# led_board_v2-3hole.net
KiCad netlist of a schematic drawn in EAGLE
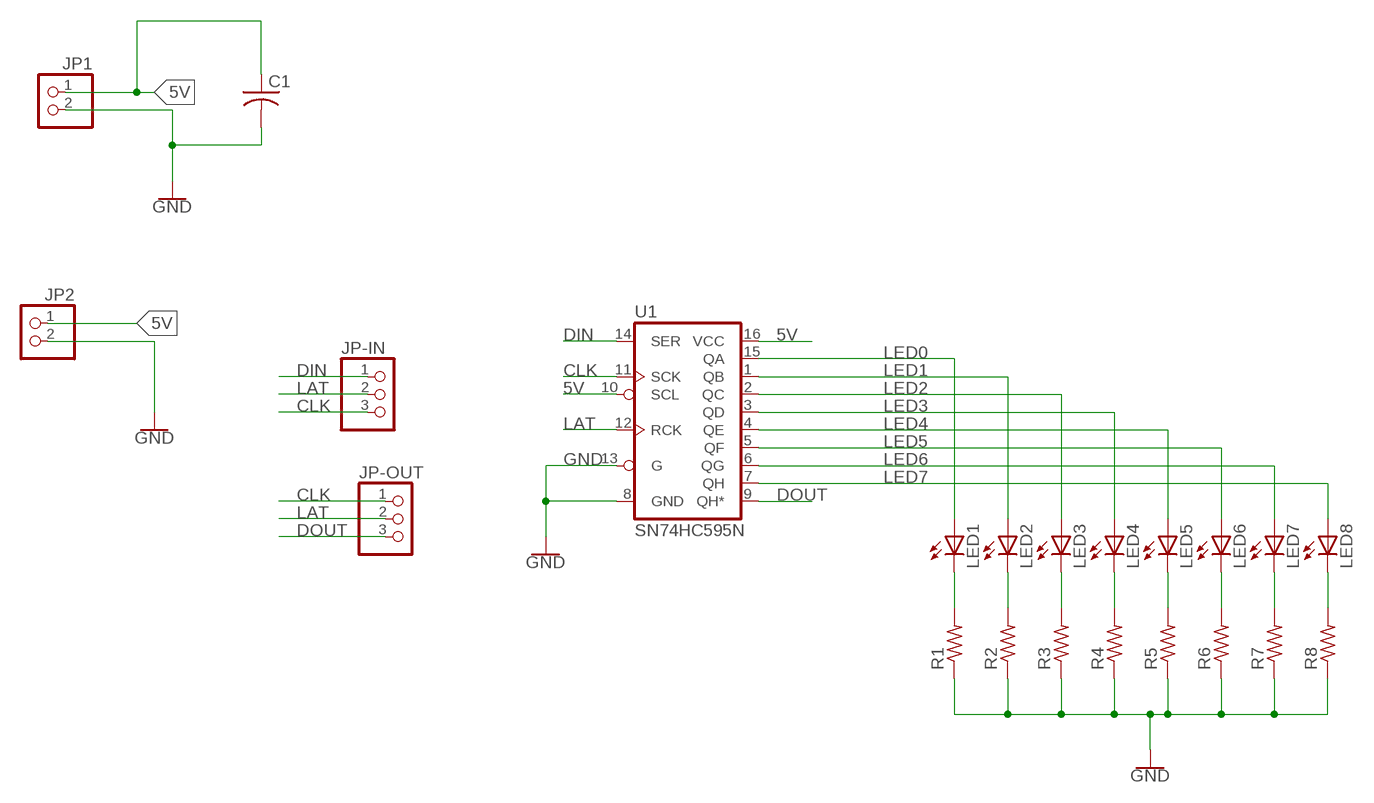
[diagram p0: schematic, sheet 1]

(export (version "E")
  (design (tool "Eeschema 10.0.6"))
  (components
    (comp (ref "C1")
      (value "C-US025-030X050")
      (footprint "eagle-import:C025-030X050")
      (libsource (lib "eagle-import") (part "C-US025-030X050"))
    )
    (comp (ref "JP-IN")
      (value "PINHD-1X3")
      (footprint "eagle-import:1X03")
      (libsource (lib "eagle-import") (part "PINHD-1X3"))
    )
    (comp (ref "JP-OUT")
      (value "PINHD-1X3")
      (footprint "eagle-import:1X03")
      (libsource (lib "eagle-import") (part "PINHD-1X3"))
    )
    (comp (ref "JP1")
      (value "PINHD-1X2")
      (footprint "eagle-import:1X02")
      (libsource (lib "eagle-import") (part "PINHD-1X2"))
    )
    (comp (ref "JP2")
      (value "PINHD-1X2")
      (footprint "eagle-import:1X02")
      (libsource (lib "eagle-import") (part "PINHD-1X2"))
    )
    (comp (ref "LED1")
      (value "LED3MM")
      (footprint "eagle-import:LED3MM")
      (libsource (lib "eagle-import") (part "LED3MM"))
    )
    (comp (ref "LED2")
      (value "LED3MM")
      (footprint "eagle-import:LED3MM")
      (libsource (lib "eagle-import") (part "LED3MM"))
    )
    (comp (ref "LED3")
      (value "LED3MM")
      (footprint "eagle-import:LED3MM")
      (libsource (lib "eagle-import") (part "LED3MM"))
    )
    (comp (ref "LED4")
      (value "LED3MM")
      (footprint "eagle-import:LED3MM")
      (libsource (lib "eagle-import") (part "LED3MM"))
    )
    (comp (ref "LED5")
      (value "LED3MM")
      (footprint "eagle-import:LED3MM")
      (libsource (lib "eagle-import") (part "LED3MM"))
    )
    (comp (ref "LED6")
      (value "LED3MM")
      (footprint "eagle-import:LED3MM")
      (libsource (lib "eagle-import") (part "LED3MM"))
    )
    (comp (ref "LED7")
      (value "LED3MM")
      (footprint "eagle-import:LED3MM")
      (libsource (lib "eagle-import") (part "LED3MM"))
    )
    (comp (ref "LED8")
      (value "LED3MM")
      (footprint "eagle-import:LED3MM")
      (libsource (lib "eagle-import") (part "LED3MM"))
    )
    (comp (ref "R1")
      (value "R-US_0207/7")
      (footprint "eagle-import:0207_7")
      (libsource (lib "eagle-import") (part "R-US_0207/7"))
    )
    (comp (ref "R2")
      (value "R-US_0207/7")
      (footprint "eagle-import:0207_7")
      (libsource (lib "eagle-import") (part "R-US_0207/7"))
    )
    (comp (ref "R3")
      (value "R-US_0207/7")
      (footprint "eagle-import:0207_7")
      (libsource (lib "eagle-import") (part "R-US_0207/7"))
    )
    (comp (ref "R4")
      (value "R-US_0207/7")
      (footprint "eagle-import:0207_7")
      (libsource (lib "eagle-import") (part "R-US_0207/7"))
    )
    (comp (ref "R5")
      (value "R-US_0207/7")
      (footprint "eagle-import:0207_7")
      (libsource (lib "eagle-import") (part "R-US_0207/7"))
    )
    (comp (ref "R6")
      (value "R-US_0207/7")
      (footprint "eagle-import:0207_7")
      (libsource (lib "eagle-import") (part "R-US_0207/7"))
    )
    (comp (ref "R7")
      (value "R-US_0207/7")
      (footprint "eagle-import:0207_7")
      (libsource (lib "eagle-import") (part "R-US_0207/7"))
    )
    (comp (ref "R8")
      (value "R-US_0207/7")
      (footprint "eagle-import:0207_7")
      (libsource (lib "eagle-import") (part "R-US_0207/7"))
    )
    (comp (ref "U1")
      (value "SN74HC595N")
      (footprint "eagle-import:DIP16")
      (libsource (lib "eagle-import") (part "74595NHC"))
    )
  )
  (nets
    (net (code "1") (name "/CLK") (class "Default")
      (node (ref "JP-IN") (pin "3") (pinfunction "3_3") (pintype "passive"))
      (node (ref "JP-OUT") (pin "1") (pinfunction "1_1") (pintype "passive"))
      (node (ref "U1") (pin "11") (pinfunction "SCK_11") (pintype "input"))
    )
    (net (code "2") (name "/DIN") (class "Default")
      (node (ref "JP-IN") (pin "1") (pinfunction "1_1") (pintype "passive"))
      (node (ref "U1") (pin "14") (pinfunction "SER_14") (pintype "input"))
    )
    (net (code "3") (name "/DOUT") (class "Default")
      (node (ref "JP-OUT") (pin "3") (pinfunction "3_3") (pintype "passive"))
      (node (ref "U1") (pin "9") (pinfunction "QH*_9") (pintype "tri_state"))
    )
    (net (code "4") (name "/LAT") (class "Default")
      (node (ref "JP-IN") (pin "2") (pinfunction "2_2") (pintype "passive"))
      (node (ref "JP-OUT") (pin "2") (pinfunction "2_2") (pintype "passive"))
      (node (ref "U1") (pin "12") (pinfunction "RCK_12") (pintype "input"))
    )
    (net (code "5") (name "/LED0") (class "Default")
      (node (ref "LED1") (pin "A") (pinfunction "A_A") (pintype "passive"))
      (node (ref "U1") (pin "15") (pinfunction "QA_15") (pintype "tri_state"))
    )
    (net (code "6") (name "/LED1") (class "Default")
      (node (ref "LED2") (pin "A") (pinfunction "A_A") (pintype "passive"))
      (node (ref "U1") (pin "1") (pinfunction "QB_1") (pintype "tri_state"))
    )
    (net (code "7") (name "/LED2") (class "Default")
      (node (ref "LED3") (pin "A") (pinfunction "A_A") (pintype "passive"))
      (node (ref "U1") (pin "2") (pinfunction "QC_2") (pintype "tri_state"))
    )
    (net (code "8") (name "/LED3") (class "Default")
      (node (ref "LED4") (pin "A") (pinfunction "A_A") (pintype "passive"))
      (node (ref "U1") (pin "3") (pinfunction "QD_3") (pintype "tri_state"))
    )
    (net (code "9") (name "/LED4") (class "Default")
      (node (ref "LED5") (pin "A") (pinfunction "A_A") (pintype "passive"))
      (node (ref "U1") (pin "4") (pinfunction "QE_4") (pintype "tri_state"))
    )
    (net (code "10") (name "/LED5") (class "Default")
      (node (ref "LED6") (pin "A") (pinfunction "A_A") (pintype "passive"))
      (node (ref "U1") (pin "5") (pinfunction "QF_5") (pintype "tri_state"))
    )
    (net (code "11") (name "/LED6") (class "Default")
      (node (ref "LED7") (pin "A") (pinfunction "A_A") (pintype "passive"))
      (node (ref "U1") (pin "6") (pinfunction "QG_6") (pintype "tri_state"))
    )
    (net (code "12") (name "/LED7") (class "Default")
      (node (ref "LED8") (pin "A") (pinfunction "A_A") (pintype "passive"))
      (node (ref "U1") (pin "7") (pinfunction "QH_7") (pintype "tri_state"))
    )
    (net (code "13") (name "5V") (class "Default")
      (node (ref "C1") (pin "1") (pinfunction "1_1") (pintype "passive"))
      (node (ref "JP1") (pin "1") (pinfunction "1_1") (pintype "passive"))
      (node (ref "JP2") (pin "1") (pinfunction "1_1") (pintype "passive"))
      (node (ref "U1") (pin "10") (pinfunction "SCL_10") (pintype "input"))
      (node (ref "U1") (pin "16") (pinfunction "VCC_16") (pintype "power_in"))
    )
    (net (code "14") (name "GND") (class "Default")
      (node (ref "C1") (pin "2") (pinfunction "2_2") (pintype "passive"))
      (node (ref "JP1") (pin "2") (pinfunction "2_2") (pintype "passive"))
      (node (ref "JP2") (pin "2") (pinfunction "2_2") (pintype "passive"))
      (node (ref "R1") (pin "1") (pinfunction "1_1") (pintype "passive"))
      (node (ref "R2") (pin "1") (pinfunction "1_1") (pintype "passive"))
      (node (ref "R3") (pin "1") (pinfunction "1_1") (pintype "passive"))
      (node (ref "R4") (pin "1") (pinfunction "1_1") (pintype "passive"))
      (node (ref "R5") (pin "1") (pinfunction "1_1") (pintype "passive"))
      (node (ref "R6") (pin "1") (pinfunction "1_1") (pintype "passive"))
      (node (ref "R7") (pin "1") (pinfunction "1_1") (pintype "passive"))
      (node (ref "R8") (pin "1") (pinfunction "1_1") (pintype "passive"))
      (node (ref "U1") (pin "13") (pinfunction "G_13") (pintype "input"))
      (node (ref "U1") (pin "8") (pinfunction "GND_8") (pintype "power_in"))
    )
    (net (code "15") (name "Net-(LED1-C)") (class "Default")
      (node (ref "LED1") (pin "K") (pinfunction "C_K") (pintype "passive"))
      (node (ref "R1") (pin "2") (pinfunction "2_2") (pintype "passive"))
    )
    (net (code "16") (name "Net-(LED2-C)") (class "Default")
      (node (ref "LED2") (pin "K") (pinfunction "C_K") (pintype "passive"))
      (node (ref "R2") (pin "2") (pinfunction "2_2") (pintype "passive"))
    )
    (net (code "17") (name "Net-(LED3-C)") (class "Default")
      (node (ref "LED3") (pin "K") (pinfunction "C_K") (pintype "passive"))
      (node (ref "R3") (pin "2") (pinfunction "2_2") (pintype "passive"))
    )
    (net (code "18") (name "Net-(LED4-C)") (class "Default")
      (node (ref "LED4") (pin "K") (pinfunction "C_K") (pintype "passive"))
      (node (ref "R4") (pin "2") (pinfunction "2_2") (pintype "passive"))
    )
    (net (code "19") (name "Net-(LED5-C)") (class "Default")
      (node (ref "LED5") (pin "K") (pinfunction "C_K") (pintype "passive"))
      (node (ref "R5") (pin "2") (pinfunction "2_2") (pintype "passive"))
    )
    (net (code "20") (name "Net-(LED6-C)") (class "Default")
      (node (ref "LED6") (pin "K") (pinfunction "C_K") (pintype "passive"))
      (node (ref "R6") (pin "2") (pinfunction "2_2") (pintype "passive"))
    )
    (net (code "21") (name "Net-(LED7-C)") (class "Default")
      (node (ref "LED7") (pin "K") (pinfunction "C_K") (pintype "passive"))
      (node (ref "R7") (pin "2") (pinfunction "2_2") (pintype "passive"))
    )
    (net (code "22") (name "Net-(LED8-C)") (class "Default")
      (node (ref "LED8") (pin "K") (pinfunction "C_K") (pintype "passive"))
      (node (ref "R8") (pin "2") (pinfunction "2_2") (pintype "passive"))
    )
  )
)
